# 01-USER_IO.net
KiCad netlist of a schematic drawn in Altium Designer
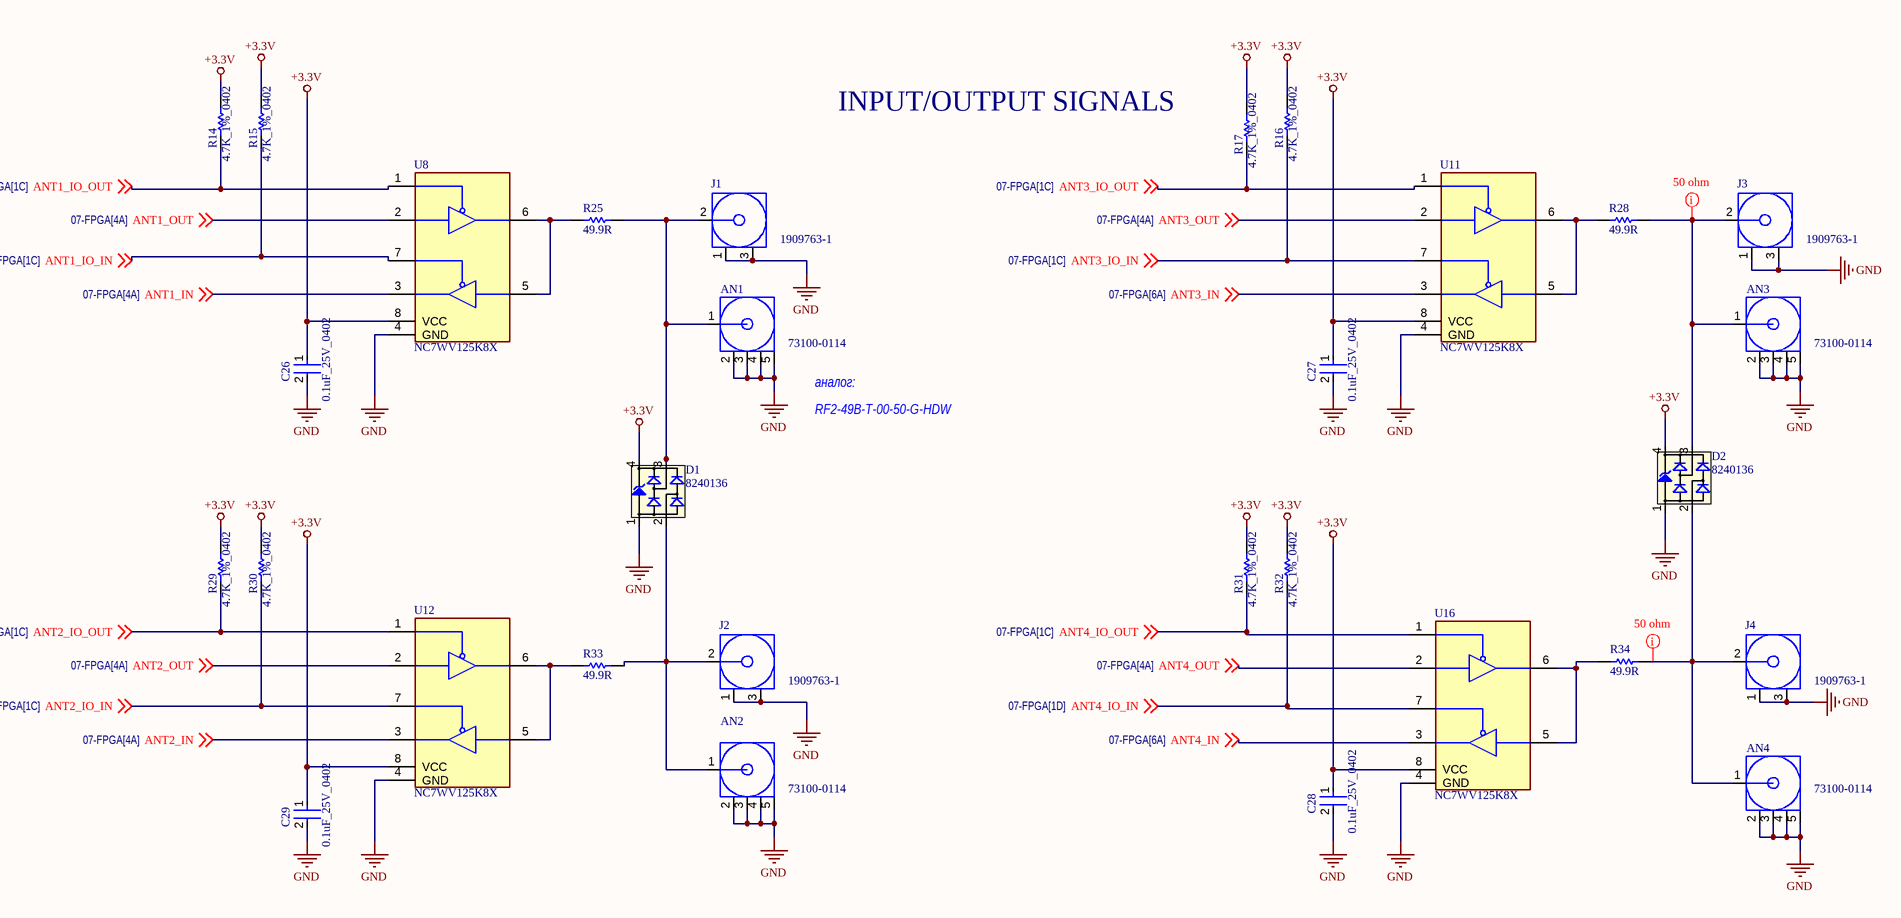
[diagram p0: 01-USER_IO.SchDoc]

(export (version "E")
  (design (tool "Eeschema 10.0.6"))
  (components
    (comp (ref "AN1")
      (value "73100-0114")
      (footprint "SamacSys:731000114")
      (description "Connector")
      (fields (field (name "MOUSER PART NUMBER") "538-73100-0114"))
      (libsource (lib "SamacSys") (part "73100-0114"))
    )
    (comp (ref "AN2")
      (value "73100-0114")
      (footprint "SamacSys:731000114")
      (description "Connector")
      (fields (field (name "MOUSER PART NUMBER") "538-73100-0114"))
      (libsource (lib "SamacSys") (part "73100-0114"))
    )
    (comp (ref "AN3")
      (value "73100-0114")
      (footprint "SamacSys:731000114")
      (description "Connector")
      (fields (field (name "MOUSER PART NUMBER") "538-73100-0114"))
      (libsource (lib "SamacSys") (part "73100-0114"))
    )
    (comp (ref "AN4")
      (value "73100-0114")
      (footprint "SamacSys:731000114")
      (description "Connector")
      (fields (field (name "MOUSER PART NUMBER") "538-73100-0114"))
      (libsource (lib "SamacSys") (part "73100-0114"))
    )
    (comp (ref "C26")
      (value "0.1uF_25V_0402")
      (footprint "FP-0402-L_1_0_1-W_0_5_0_1-IPC_C")
      (description "General Purpose Ceramic Capacitor, 0402, 100nF, 10%, X7R, 15%, 25V")
      (fields (field (name "VOLTAGE") "25V") (field (name "TOLERANCE") "10%"))
      (libsource (lib "Altium Content Vault") (part "b4654b650e69147ec39a6b967a45e02"))
    )
    (comp (ref "C27")
      (value "0.1uF_25V_0402")
      (footprint "FP-0402-L_1_0_1-W_0_5_0_1-IPC_C")
      (description "General Purpose Ceramic Capacitor, 0402, 100nF, 10%, X7R, 15%, 25V")
      (fields (field (name "VOLTAGE") "25V") (field (name "TOLERANCE") "10%"))
      (libsource (lib "Altium Content Vault") (part "b4654b650e69147ec39a6b967a45e02"))
    )
    (comp (ref "C28")
      (value "0.1uF_25V_0402")
      (footprint "FP-0402-L_1_0_1-W_0_5_0_1-IPC_C")
      (description "General Purpose Ceramic Capacitor, 0402, 100nF, 10%, X7R, 15%, 25V")
      (fields (field (name "VOLTAGE") "25V") (field (name "TOLERANCE") "10%"))
      (libsource (lib "Altium Content Vault") (part "b4654b650e69147ec39a6b967a45e02"))
    )
    (comp (ref "C29")
      (value "0.1uF_25V_0402")
      (footprint "FP-0402-L_1_0_1-W_0_5_0_1-IPC_C")
      (description "General Purpose Ceramic Capacitor, 0402, 100nF, 10%, X7R, 15%, 25V")
      (fields (field (name "VOLTAGE") "25V") (field (name "TOLERANCE") "10%"))
      (libsource (lib "Altium Content Vault") (part "b4654b650e69147ec39a6b967a45e02"))
    )
    (comp (ref "D1")
      (value "8240136")
      (footprint "SOT143-4L")
      (description "TVS Diode WE-TVS-HS, VRWM=3.3V")
      (fields (field (name "MANUFACTURER") "Wuerth Elektronik"))
      (libsource (lib "Altium Content Vault") (part "WE-TVS-HS-4"))
    )
    (comp (ref "D2")
      (value "8240136")
      (footprint "SOT143-4L")
      (description "TVS Diode WE-TVS-HS, VRWM=3.3V")
      (fields (field (name "MANUFACTURER") "Wuerth Elektronik"))
      (libsource (lib "Altium Content Vault") (part "WE-TVS-HS-4"))
    )
    (comp (ref "J1")
      (value "1909763-1")
      (footprint "TECO-1909763-1_V")
      (description "Ultra Miniature Coaxial Connector Jack, 60 V, 50 Ohm, -40 to 90 degC, RoHS, Tape and Reel")
      (fields (field (name "MANUFACTURER") "TE Connectivity"))
      (libsource (lib "Altium Content Vault") (part "CN-1P-M-RF3"))
    )
    (comp (ref "J2")
      (value "1909763-1")
      (footprint "TECO-1909763-1_V")
      (description "Ultra Miniature Coaxial Connector Jack, 60 V, 50 Ohm, -40 to 90 degC, RoHS, Tape and Reel")
      (fields (field (name "MANUFACTURER") "TE Connectivity"))
      (libsource (lib "Altium Content Vault") (part "CN-1P-M-RF3"))
    )
    (comp (ref "J3")
      (value "1909763-1")
      (footprint "TECO-1909763-1_V")
      (description "Ultra Miniature Coaxial Connector Jack, 60 V, 50 Ohm, -40 to 90 degC, RoHS, Tape and Reel")
      (fields (field (name "MANUFACTURER") "TE Connectivity"))
      (libsource (lib "Altium Content Vault") (part "CN-1P-M-RF3"))
    )
    (comp (ref "J4")
      (value "1909763-1")
      (footprint "TECO-1909763-1_V")
      (description "Ultra Miniature Coaxial Connector Jack, 60 V, 50 Ohm, -40 to 90 degC, RoHS, Tape and Reel")
      (fields (field (name "MANUFACTURER") "TE Connectivity"))
      (libsource (lib "Altium Content Vault") (part "CN-1P-M-RF3"))
    )
    (comp (ref "R14")
      (value "4.7K_1%_0402")
      (footprint "RESC1005X40X25NL10T10")
      (fields (field (name "MANUFACTURER") "Bourns") (field (name "PART NUMBER") "CR0402-FX-4701GLF"))
      (libsource (lib "Altium Content Vault") (part "RES"))
    )
    (comp (ref "R15")
      (value "4.7K_1%_0402")
      (footprint "RESC1005X40X25NL10T10")
      (fields (field (name "MANUFACTURER") "Bourns") (field (name "PART NUMBER") "CR0402-FX-4701GLF"))
      (libsource (lib "Altium Content Vault") (part "RES"))
    )
    (comp (ref "R16")
      (value "4.7K_1%_0402")
      (footprint "RESC1005X40X25NL10T10")
      (fields (field (name "MANUFACTURER") "Bourns") (field (name "PART NUMBER") "CR0402-FX-4701GLF"))
      (libsource (lib "Altium Content Vault") (part "RES"))
    )
    (comp (ref "R17")
      (value "4.7K_1%_0402")
      (footprint "RESC1005X40X25NL10T10")
      (fields (field (name "MANUFACTURER") "Bourns") (field (name "PART NUMBER") "CR0402-FX-4701GLF"))
      (libsource (lib "Altium Content Vault") (part "RES"))
    )
    (comp (ref "R25")
      (value "49.9R")
      (footprint "RESC1608X55X25NL10T15")
      (libsource (lib "Altium Content Vault") (part "RES-2"))
    )
    (comp (ref "R28")
      (value "49.9R")
      (footprint "RESC1608X55X25NL10T15")
      (libsource (lib "Altium Content Vault") (part "RES-2"))
    )
    (comp (ref "R29")
      (value "4.7K_1%_0402")
      (footprint "RESC1005X40X25NL10T10")
      (fields (field (name "MANUFACTURER") "Bourns") (field (name "PART NUMBER") "CR0402-FX-4701GLF"))
      (libsource (lib "Altium Content Vault") (part "RES"))
    )
    (comp (ref "R30")
      (value "4.7K_1%_0402")
      (footprint "RESC1005X40X25NL10T10")
      (fields (field (name "MANUFACTURER") "Bourns") (field (name "PART NUMBER") "CR0402-FX-4701GLF"))
      (libsource (lib "Altium Content Vault") (part "RES"))
    )
    (comp (ref "R31")
      (value "4.7K_1%_0402")
      (footprint "RESC1005X40X25NL10T10")
      (fields (field (name "MANUFACTURER") "Bourns") (field (name "PART NUMBER") "CR0402-FX-4701GLF"))
      (libsource (lib "Altium Content Vault") (part "RES"))
    )
    (comp (ref "R32")
      (value "4.7K_1%_0402")
      (footprint "RESC1005X40X25NL10T10")
      (fields (field (name "MANUFACTURER") "Bourns") (field (name "PART NUMBER") "CR0402-FX-4701GLF"))
      (libsource (lib "Altium Content Vault") (part "RES"))
    )
    (comp (ref "R33")
      (value "49.9R")
      (footprint "RESC1608X55X25NL10T15")
      (libsource (lib "Altium Content Vault") (part "RES-2"))
    )
    (comp (ref "R34")
      (value "49.9R")
      (footprint "RESC1608X55X25NL10T15")
      (libsource (lib "Altium Content Vault") (part "RES-2"))
    )
    (comp (ref "U8")
      (value "NC7WV125K8X")
      (footprint "SamacSys:SOP50P310X90-8N")
      (description "Integrated Circuit")
      (fields (field (name "MOUSER PART NUMBER") "512-NC7WV125K8X"))
      (libsource (lib "SamacSys") (part "NC7WV125K8X"))
    )
    (comp (ref "U11")
      (value "NC7WV125K8X")
      (footprint "SamacSys:SOP50P310X90-8N")
      (description "Integrated Circuit")
      (fields (field (name "MOUSER PART NUMBER") "512-NC7WV125K8X"))
      (libsource (lib "SamacSys") (part "NC7WV125K8X"))
    )
    (comp (ref "U12")
      (value "NC7WV125K8X")
      (footprint "SamacSys:SOP50P310X90-8N")
      (description "Integrated Circuit")
      (fields (field (name "MOUSER PART NUMBER") "512-NC7WV125K8X"))
      (libsource (lib "SamacSys") (part "NC7WV125K8X"))
    )
    (comp (ref "U16")
      (value "NC7WV125K8X")
      (footprint "SamacSys:SOP50P310X90-8N")
      (description "Integrated Circuit")
      (fields (field (name "MOUSER PART NUMBER") "512-NC7WV125K8X"))
      (libsource (lib "SamacSys") (part "NC7WV125K8X"))
    )
  )
  (nets
    (net (code "1") (name "+3.3V") (class "Default")
      (node (ref "C26") (pin "1") (pinfunction "1_1") (pintype "passive"))
      (node (ref "C27") (pin "1") (pinfunction "1_1") (pintype "passive"))
      (node (ref "C28") (pin "1") (pinfunction "1_1") (pintype "passive"))
      (node (ref "C29") (pin "1") (pinfunction "1_1") (pintype "passive"))
      (node (ref "D1") (pin "4") (pinfunction "VDD_4") (pintype "passive"))
      (node (ref "D2") (pin "4") (pinfunction "VDD_4") (pintype "passive"))
      (node (ref "R14") (pin "1") (pinfunction "1_1") (pintype "passive"))
      (node (ref "R15") (pin "1") (pinfunction "1_1") (pintype "passive"))
      (node (ref "R16") (pin "1") (pinfunction "1_1") (pintype "passive"))
      (node (ref "R17") (pin "1") (pinfunction "1_1") (pintype "passive"))
      (node (ref "R29") (pin "1") (pinfunction "1_1") (pintype "passive"))
      (node (ref "R30") (pin "1") (pinfunction "1_1") (pintype "passive"))
      (node (ref "R31") (pin "1") (pinfunction "1_1") (pintype "passive"))
      (node (ref "R32") (pin "1") (pinfunction "1_1") (pintype "passive"))
      (node (ref "U11") (pin "8") (pinfunction "VCC_8") (pintype "passive"))
      (node (ref "U12") (pin "8") (pinfunction "VCC_8") (pintype "passive"))
      (node (ref "U16") (pin "8") (pinfunction "VCC_8") (pintype "passive"))
      (node (ref "U8") (pin "8") (pinfunction "VCC_8") (pintype "passive"))
    )
    (net (code "2") (name "ANT1_IN") (class "Default") (node (ref "U8") (pin "3") (pintype "passive")))
    (net (code "3") (name "ANT1_IO_IN") (class "Default")
      (node (ref "R15") (pin "2") (pinfunction "2_2") (pintype "passive"))
      (node (ref "U8") (pin "7") (pintype "passive"))
    )
    (net (code "4") (name "ANT1_IO_OUT") (class "Default")
      (node (ref "R14") (pin "2") (pinfunction "2_2") (pintype "passive"))
      (node (ref "U8") (pin "1") (pintype "passive"))
    )
    (net (code "5") (name "ANT1_OUT") (class "Default") (node (ref "U8") (pin "2") (pintype "passive")))
    (net (code "6") (name "ANT2_IN") (class "Default") (node (ref "U12") (pin "3") (pintype "passive")))
    (net (code "7") (name "ANT2_IO_IN") (class "Default")
      (node (ref "R30") (pin "2") (pinfunction "2_2") (pintype "passive"))
      (node (ref "U12") (pin "7") (pintype "passive"))
    )
    (net (code "8") (name "ANT2_IO_OUT") (class "Default")
      (node (ref "R29") (pin "2") (pinfunction "2_2") (pintype "passive"))
      (node (ref "U12") (pin "1") (pintype "passive"))
    )
    (net (code "9") (name "ANT2_OUT") (class "Default") (node (ref "U12") (pin "2") (pintype "passive")))
    (net (code "10") (name "ANT3_IN") (class "Default") (node (ref "U11") (pin "3") (pintype "passive")))
    (net (code "11") (name "ANT3_IO_IN") (class "Default")
      (node (ref "R16") (pin "2") (pinfunction "2_2") (pintype "passive"))
      (node (ref "U11") (pin "7") (pintype "passive"))
    )
    (net (code "12") (name "ANT3_IO_OUT") (class "Default")
      (node (ref "R17") (pin "2") (pinfunction "2_2") (pintype "passive"))
      (node (ref "U11") (pin "1") (pintype "passive"))
    )
    (net (code "13") (name "ANT3_OUT") (class "Default") (node (ref "U11") (pin "2") (pintype "passive")))
    (net (code "14") (name "ANT4_IN") (class "Default") (node (ref "U16") (pin "3") (pintype "passive")))
    (net (code "15") (name "ANT4_IO_IN") (class "Default")
      (node (ref "R32") (pin "2") (pinfunction "2_2") (pintype "passive"))
      (node (ref "U16") (pin "7") (pintype "passive"))
    )
    (net (code "16") (name "ANT4_IO_OUT") (class "Default")
      (node (ref "R31") (pin "2") (pinfunction "2_2") (pintype "passive"))
      (node (ref "U16") (pin "1") (pintype "passive"))
    )
    (net (code "17") (name "ANT4_OUT") (class "Default") (node (ref "U16") (pin "2") (pintype "passive")))
    (net (code "18") (name "GND") (class "Default")
      (node (ref "AN1") (pin "2") (pinfunction "2_2") (pintype "passive"))
      (node (ref "AN1") (pin "3") (pinfunction "3_3") (pintype "passive"))
      (node (ref "AN1") (pin "4") (pinfunction "4_4") (pintype "passive"))
      (node (ref "AN1") (pin "5") (pinfunction "5_5") (pintype "passive"))
      (node (ref "AN2") (pin "2") (pinfunction "2_2") (pintype "passive"))
      (node (ref "AN2") (pin "3") (pinfunction "3_3") (pintype "passive"))
      (node (ref "AN2") (pin "4") (pinfunction "4_4") (pintype "passive"))
      (node (ref "AN2") (pin "5") (pinfunction "5_5") (pintype "passive"))
      (node (ref "AN3") (pin "2") (pinfunction "2_2") (pintype "passive"))
      (node (ref "AN3") (pin "3") (pinfunction "3_3") (pintype "passive"))
      (node (ref "AN3") (pin "4") (pinfunction "4_4") (pintype "passive"))
      (node (ref "AN3") (pin "5") (pinfunction "5_5") (pintype "passive"))
      (node (ref "AN4") (pin "2") (pinfunction "2_2") (pintype "passive"))
      (node (ref "AN4") (pin "3") (pinfunction "3_3") (pintype "passive"))
      (node (ref "AN4") (pin "4") (pinfunction "4_4") (pintype "passive"))
      (node (ref "AN4") (pin "5") (pinfunction "5_5") (pintype "passive"))
      (node (ref "C26") (pin "2") (pinfunction "2_2") (pintype "passive"))
      (node (ref "C27") (pin "2") (pinfunction "2_2") (pintype "passive"))
      (node (ref "C28") (pin "2") (pinfunction "2_2") (pintype "passive"))
      (node (ref "C29") (pin "2") (pinfunction "2_2") (pintype "passive"))
      (node (ref "D1") (pin "1") (pinfunction "GND_1") (pintype "passive"))
      (node (ref "D2") (pin "1") (pinfunction "GND_1") (pintype "passive"))
      (node (ref "J1") (pin "1") (pinfunction "1_1") (pintype "passive"))
      (node (ref "J1") (pin "3") (pinfunction "3_3") (pintype "passive"))
      (node (ref "J2") (pin "1") (pinfunction "1_1") (pintype "passive"))
      (node (ref "J2") (pin "3") (pinfunction "3_3") (pintype "passive"))
      (node (ref "J3") (pin "1") (pinfunction "1_1") (pintype "passive"))
      (node (ref "J3") (pin "3") (pinfunction "3_3") (pintype "passive"))
      (node (ref "J4") (pin "1") (pinfunction "1_1") (pintype "passive"))
      (node (ref "J4") (pin "3") (pinfunction "3_3") (pintype "passive"))
      (node (ref "U11") (pin "4") (pinfunction "GND_4") (pintype "passive"))
      (node (ref "U12") (pin "4") (pinfunction "GND_4") (pintype "passive"))
      (node (ref "U16") (pin "4") (pinfunction "GND_4") (pintype "passive"))
      (node (ref "U8") (pin "4") (pinfunction "GND_4") (pintype "passive"))
    )
    (net (code "19") (name "Net-(D1-I{slash}O1)") (class "Default")
      (node (ref "AN2") (pin "1") (pinfunction "1_1") (pintype "passive"))
      (node (ref "D1") (pin "2") (pinfunction "I/O1_2") (pintype "passive"))
      (node (ref "J2") (pin "2") (pinfunction "2_2") (pintype "passive"))
      (node (ref "R33") (pin "2") (pinfunction "2_2") (pintype "passive"))
    )
    (net (code "20") (name "Net-(D1-I{slash}O2)") (class "Default")
      (node (ref "AN1") (pin "1") (pinfunction "1_1") (pintype "passive"))
      (node (ref "D1") (pin "3") (pinfunction "I/O2_3") (pintype "passive"))
      (node (ref "J1") (pin "2") (pinfunction "2_2") (pintype "passive"))
      (node (ref "R25") (pin "2") (pinfunction "2_2") (pintype "passive"))
    )
    (net (code "21") (name "Net-(D2-I{slash}O1)") (class "Default")
      (node (ref "AN4") (pin "1") (pinfunction "1_1") (pintype "passive"))
      (node (ref "D2") (pin "2") (pinfunction "I/O1_2") (pintype "passive"))
      (node (ref "J4") (pin "2") (pinfunction "2_2") (pintype "passive"))
      (node (ref "R34") (pin "2") (pinfunction "2_2") (pintype "passive"))
    )
    (net (code "22") (name "Net-(D2-I{slash}O2)") (class "Default")
      (node (ref "AN3") (pin "1") (pinfunction "1_1") (pintype "passive"))
      (node (ref "D2") (pin "3") (pinfunction "I/O2_3") (pintype "passive"))
      (node (ref "J3") (pin "2") (pinfunction "2_2") (pintype "passive"))
      (node (ref "R28") (pin "2") (pinfunction "2_2") (pintype "passive"))
    )
    (net (code "23") (name "Net-(R25-Pad1)") (class "Default")
      (node (ref "R25") (pin "1") (pinfunction "1_1") (pintype "passive"))
      (node (ref "U8") (pin "5") (pintype "passive"))
      (node (ref "U8") (pin "6") (pintype "passive"))
    )
    (net (code "24") (name "Net-(R28-Pad1)") (class "Default")
      (node (ref "R28") (pin "1") (pinfunction "1_1") (pintype "passive"))
      (node (ref "U11") (pin "5") (pintype "passive"))
      (node (ref "U11") (pin "6") (pintype "passive"))
    )
    (net (code "25") (name "Net-(R33-Pad1)") (class "Default")
      (node (ref "R33") (pin "1") (pinfunction "1_1") (pintype "passive"))
      (node (ref "U12") (pin "5") (pintype "passive"))
      (node (ref "U12") (pin "6") (pintype "passive"))
    )
    (net (code "26") (name "Net-(R34-Pad1)") (class "Default")
      (node (ref "R34") (pin "1") (pinfunction "1_1") (pintype "passive"))
      (node (ref "U16") (pin "5") (pintype "passive"))
      (node (ref "U16") (pin "6") (pintype "passive"))
    )
  )
)
